# pcb_univ_3-8-0-x-rev2.net
KiCad netlist of a schematic drawn in EAGLE
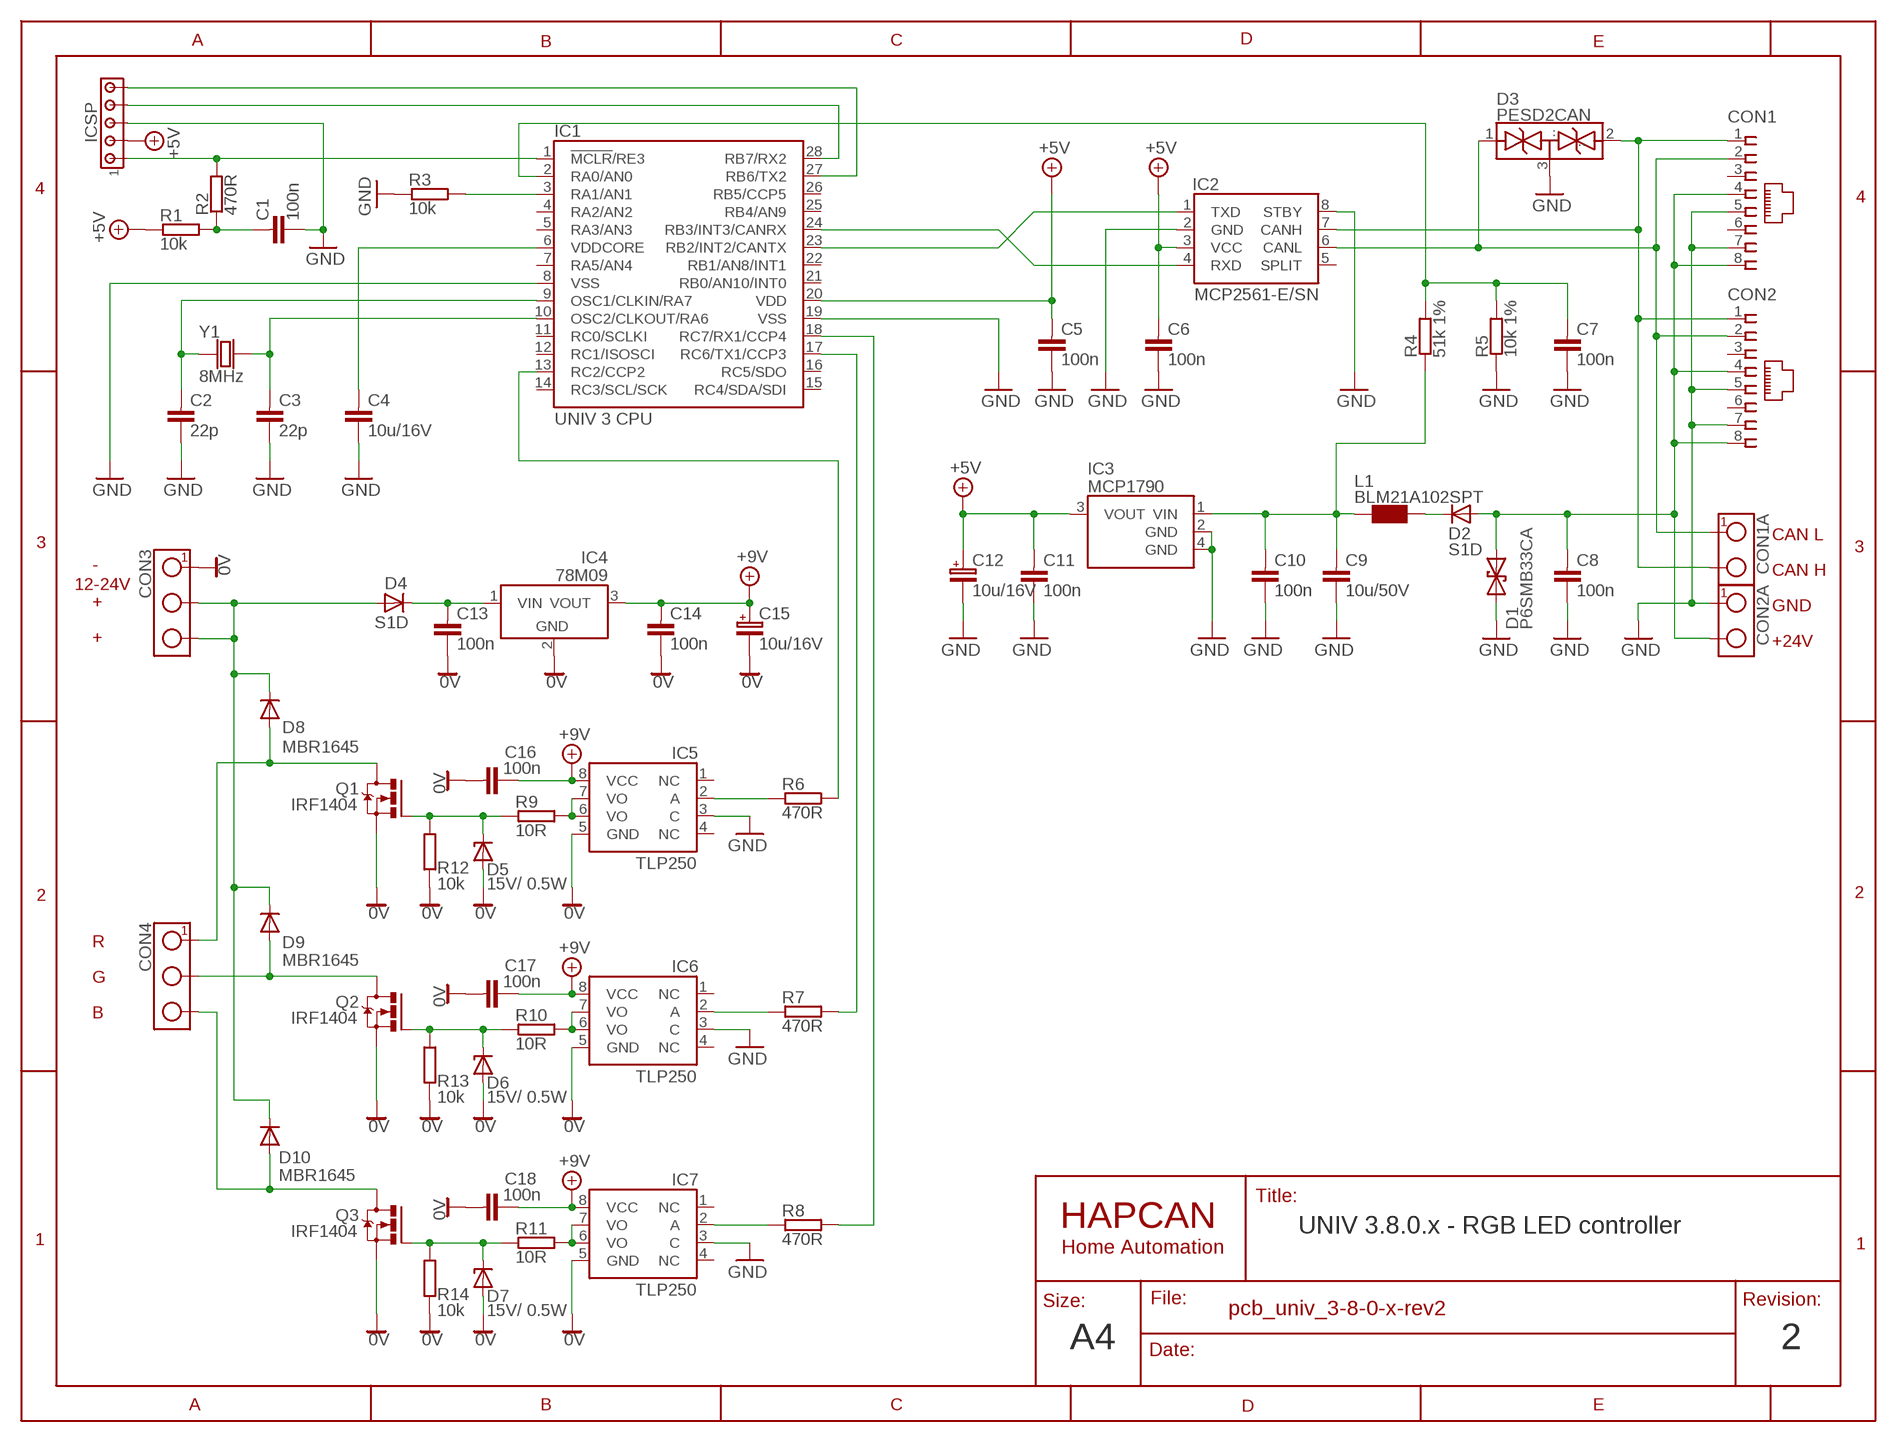
[diagram p0: schematic, sheet 1]

(export (version "E")
  (design (tool "Eeschema 10.0.6"))
  (components
    (comp (ref "C1")
      (value "100n")
      (footprint "eagle-import:0805")
      (libsource (lib "eagle-import") (part "CAPACITOR0805"))
    )
    (comp (ref "C2")
      (value "22p")
      (footprint "eagle-import:0805")
      (libsource (lib "eagle-import") (part "CAPACITOR0805"))
    )
    (comp (ref "C3")
      (value "22p")
      (footprint "eagle-import:0805")
      (libsource (lib "eagle-import") (part "CAPACITOR0805"))
    )
    (comp (ref "C4")
      (value "10u/16V")
      (footprint "eagle-import:0805")
      (libsource (lib "eagle-import") (part "CAPACITOR0805"))
    )
    (comp (ref "C5")
      (value "100n")
      (footprint "eagle-import:0805")
      (libsource (lib "eagle-import") (part "CAPACITOR0805"))
    )
    (comp (ref "C6")
      (value "100n")
      (footprint "eagle-import:0805")
      (libsource (lib "eagle-import") (part "CAPACITOR0805"))
    )
    (comp (ref "C7")
      (value "100n")
      (footprint "eagle-import:0805")
      (libsource (lib "eagle-import") (part "CAPACITOR0805"))
    )
    (comp (ref "C8")
      (value "100n")
      (footprint "eagle-import:0805")
      (libsource (lib "eagle-import") (part "CAPACITOR0805"))
    )
    (comp (ref "C9")
      (value "10u/50V")
      (footprint "eagle-import:1210")
      (libsource (lib "eagle-import") (part "CAPACITOR1210"))
    )
    (comp (ref "C10")
      (value "100n")
      (footprint "eagle-import:0805")
      (libsource (lib "eagle-import") (part "CAPACITOR0805"))
    )
    (comp (ref "C11")
      (value "100n")
      (footprint "eagle-import:0805")
      (libsource (lib "eagle-import") (part "CAPACITOR0805"))
    )
    (comp (ref "C12")
      (value "10u/16V")
      (footprint "eagle-import:SMC_B")
      (libsource (lib "eagle-import") (part "CAPACITOR-POLARIZED-SMC_B"))
    )
    (comp (ref "C13")
      (value "100n")
      (footprint "eagle-import:0805")
      (libsource (lib "eagle-import") (part "CAPACITOR0805"))
    )
    (comp (ref "C14")
      (value "100n")
      (footprint "eagle-import:0805")
      (libsource (lib "eagle-import") (part "CAPACITOR0805"))
    )
    (comp (ref "C15")
      (value "10u/16V")
      (footprint "eagle-import:SMC_B")
      (libsource (lib "eagle-import") (part "CAPACITOR-POLARIZED-SMC_B"))
    )
    (comp (ref "C16")
      (value "100n")
      (footprint "eagle-import:0805")
      (libsource (lib "eagle-import") (part "CAPACITOR0805"))
    )
    (comp (ref "C17")
      (value "100n")
      (footprint "eagle-import:0805")
      (libsource (lib "eagle-import") (part "CAPACITOR0805"))
    )
    (comp (ref "C18")
      (value "100n")
      (footprint "eagle-import:0805")
      (libsource (lib "eagle-import") (part "CAPACITOR0805"))
    )
    (comp (ref "CON1")
      (value "RJ45-SOCKET")
      (footprint "eagle-import:RJ45-PCB-SOCKET")
      (libsource (lib "eagle-import") (part "RJ45-SOCKET"))
    )
    (comp (ref "CON1A")
      (value "TERMINAL-2")
      (footprint "eagle-import:ARK2-5X10,5MM")
      (libsource (lib "eagle-import") (part "TERMINAL-2-5X10,5MM"))
    )
    (comp (ref "CON2")
      (value "RJ45-SOCKET")
      (footprint "eagle-import:RJ45-PCB-SOCKET")
      (libsource (lib "eagle-import") (part "RJ45-SOCKET"))
    )
    (comp (ref "CON2A")
      (value "TERMINAL-2")
      (footprint "eagle-import:ARK2-5X10,5MM")
      (libsource (lib "eagle-import") (part "TERMINAL-2-5X10,5MM"))
    )
    (comp (ref "CON3")
      (value "TERMINAL-3")
      (footprint "eagle-import:ARK3-5X10.5MM")
      (libsource (lib "eagle-import") (part "TERMINAL-3-5X10.5MM"))
    )
    (comp (ref "CON4")
      (value "TERMINAL-3")
      (footprint "eagle-import:ARK3-5X10.5MM")
      (libsource (lib "eagle-import") (part "TERMINAL-3-5X10.5MM"))
    )
    (comp (ref "D1")
      (value "P6SMB33CA")
      (footprint "eagle-import:DO-214_TRANSIL2")
      (libsource (lib "eagle-import") (part "DIODE_TRANSIL2"))
    )
    (comp (ref "D2")
      (value "S1D")
      (footprint "eagle-import:DO-214")
      (libsource (lib "eagle-import") (part "DIODE_DO-214"))
    )
    (comp (ref "D3")
      (value "PESD2CAN")
      (footprint "eagle-import:SOT-23")
      (libsource (lib "eagle-import") (part "PESD2CANSOT-23"))
    )
    (comp (ref "D4")
      (value "S1D")
      (footprint "eagle-import:DO-214")
      (libsource (lib "eagle-import") (part "DIODE_DO-214"))
    )
    (comp (ref "D5")
      (value "15V/ 0.5W")
      (footprint "eagle-import:SOD-80")
      (libsource (lib "eagle-import") (part "DIODE_ZENER_SOD-80"))
    )
    (comp (ref "D6")
      (value "15V/ 0.5W")
      (footprint "eagle-import:SOD-80")
      (libsource (lib "eagle-import") (part "DIODE_ZENER_SOD-80"))
    )
    (comp (ref "D7")
      (value "15V/ 0.5W")
      (footprint "eagle-import:SOD-80")
      (libsource (lib "eagle-import") (part "DIODE_ZENER_SOD-80"))
    )
    (comp (ref "D8")
      (value "MBR1645")
      (footprint "eagle-import:TO220V-2")
      (libsource (lib "eagle-import") (part "DIODE_TO220V"))
    )
    (comp (ref "D9")
      (value "MBR1645")
      (footprint "eagle-import:TO220V-2")
      (libsource (lib "eagle-import") (part "DIODE_TO220V"))
    )
    (comp (ref "D10")
      (value "MBR1645")
      (footprint "eagle-import:TO220V-2")
      (libsource (lib "eagle-import") (part "DIODE_TO220V"))
    )
    (comp (ref "IC1")
      (value "UNIV 3 CPU")
      (footprint "eagle-import:UNIV3CPU")
      (libsource (lib "eagle-import") (part "UNIV3CPU"))
    )
    (comp (ref "IC2")
      (value "MCP2561-E/SN")
      (footprint "eagle-import:SO-08")
      (libsource (lib "eagle-import") (part "MCP2561-E/SN"))
    )
    (comp (ref "IC3")
      (value "MCP1790")
      (footprint "eagle-import:SOT-223")
      (libsource (lib "eagle-import") (part "MCP1790"))
    )
    (comp (ref "IC4")
      (value "78M09")
      (footprint "eagle-import:TO-252")
      (libsource (lib "eagle-import") (part "78XX-TO-252"))
    )
    (comp (ref "IC5")
      (value "TLP250")
      (footprint "eagle-import:DIL-08W")
      (libsource (lib "eagle-import") (part "TLP250_WIDE"))
    )
    (comp (ref "IC6")
      (value "TLP250")
      (footprint "eagle-import:DIL-08W")
      (libsource (lib "eagle-import") (part "TLP250_WIDE"))
    )
    (comp (ref "IC7")
      (value "TLP250")
      (footprint "eagle-import:DIL-08W")
      (libsource (lib "eagle-import") (part "TLP250_WIDE"))
    )
    (comp (ref "ICSP")
      (value "HEADER5")
      (footprint "eagle-import:SIP-5")
      (libsource (lib "eagle-import") (part "HEADER5"))
    )
    (comp (ref "L1")
      (value "BLM21A102SPT")
      (footprint "eagle-import:0805@1")
      (libsource (lib "eagle-import") (part "BLMXXX"))
    )
    (comp (ref "Q1")
      (value "IRF1404")
      (footprint "eagle-import:TO220V")
      (libsource (lib "eagle-import") (part "MOSFET-N"))
    )
    (comp (ref "Q2")
      (value "IRF1404")
      (footprint "eagle-import:TO220V")
      (libsource (lib "eagle-import") (part "MOSFET-N"))
    )
    (comp (ref "Q3")
      (value "IRF1404")
      (footprint "eagle-import:TO220V")
      (libsource (lib "eagle-import") (part "MOSFET-N"))
    )
    (comp (ref "R1")
      (value "10k")
      (footprint "eagle-import:0805")
      (libsource (lib "eagle-import") (part "RESISTOR0805"))
    )
    (comp (ref "R2")
      (value "470R")
      (footprint "eagle-import:0805")
      (libsource (lib "eagle-import") (part "RESISTOR0805"))
    )
    (comp (ref "R3")
      (value "10k")
      (footprint "eagle-import:0805")
      (libsource (lib "eagle-import") (part "RESISTOR0805"))
    )
    (comp (ref "R4")
      (value "51k 1%")
      (footprint "eagle-import:0805")
      (libsource (lib "eagle-import") (part "RESISTOR0805"))
    )
    (comp (ref "R5")
      (value "10k 1%")
      (footprint "eagle-import:0805")
      (libsource (lib "eagle-import") (part "RESISTOR0805"))
    )
    (comp (ref "R6")
      (value "470R")
      (footprint "eagle-import:0805")
      (libsource (lib "eagle-import") (part "RESISTOR0805"))
    )
    (comp (ref "R7")
      (value "470R")
      (footprint "eagle-import:0805")
      (libsource (lib "eagle-import") (part "RESISTOR0805"))
    )
    (comp (ref "R8")
      (value "470R")
      (footprint "eagle-import:0805")
      (libsource (lib "eagle-import") (part "RESISTOR0805"))
    )
    (comp (ref "R9")
      (value "10R")
      (footprint "eagle-import:0805")
      (libsource (lib "eagle-import") (part "RESISTOR0805"))
    )
    (comp (ref "R10")
      (value "10R")
      (footprint "eagle-import:0805")
      (libsource (lib "eagle-import") (part "RESISTOR0805"))
    )
    (comp (ref "R11")
      (value "10R")
      (footprint "eagle-import:0805")
      (libsource (lib "eagle-import") (part "RESISTOR0805"))
    )
    (comp (ref "R12")
      (value "10k")
      (footprint "eagle-import:0805")
      (libsource (lib "eagle-import") (part "RESISTOR0805"))
    )
    (comp (ref "R13")
      (value "10k")
      (footprint "eagle-import:0805")
      (libsource (lib "eagle-import") (part "RESISTOR0805"))
    )
    (comp (ref "R14")
      (value "10k")
      (footprint "eagle-import:0805")
      (libsource (lib "eagle-import") (part "RESISTOR0805"))
    )
    (comp (ref "Y1")
      (value "8MHz")
      (footprint "eagle-import:CRYSTAL-HC49V")
      (libsource (lib "eagle-import") (part "CRYSTAL-HC49V"))
    )
  )
  (nets
    (net (code "1") (name "+5V") (class "Default")
      (node (ref "C11") (pin "1") (pinfunction "1_1") (pintype "passive"))
      (node (ref "C12") (pin "+") (pinfunction "1_+") (pintype "passive"))
      (node (ref "C5") (pin "1") (pinfunction "1_1") (pintype "passive"))
      (node (ref "C6") (pin "1") (pinfunction "1_1") (pintype "passive"))
      (node (ref "IC1") (pin "20") (pinfunction "VDD_20") (pintype "bidirectional"))
      (node (ref "IC2") (pin "3") (pinfunction "VCC_3") (pintype "bidirectional"))
      (node (ref "IC3") (pin "3") (pinfunction "VOUT_3") (pintype "bidirectional"))
      (node (ref "ICSP") (pin "2") (pinfunction "2_2") (pintype "passive"))
      (node (ref "R1") (pin "1") (pinfunction "1_1") (pintype "passive"))
    )
    (net (code "2") (name "+9V") (class "Default")
      (node (ref "C14") (pin "1") (pinfunction "1_1") (pintype "passive"))
      (node (ref "C15") (pin "+") (pinfunction "1_+") (pintype "passive"))
      (node (ref "C16") (pin "2") (pinfunction "2_2") (pintype "passive"))
      (node (ref "C17") (pin "2") (pinfunction "2_2") (pintype "passive"))
      (node (ref "C18") (pin "2") (pinfunction "2_2") (pintype "passive"))
      (node (ref "IC4") (pin "3") (pinfunction "VOUT_3") (pintype "bidirectional"))
      (node (ref "IC5") (pin "8") (pinfunction "VCC_8") (pintype "bidirectional"))
      (node (ref "IC6") (pin "8") (pinfunction "VCC_8") (pintype "bidirectional"))
      (node (ref "IC7") (pin "8") (pinfunction "VCC_8") (pintype "bidirectional"))
    )
    (net (code "3") (name "0V") (class "Default")
      (node (ref "C13") (pin "2") (pinfunction "2_2") (pintype "passive"))
      (node (ref "C14") (pin "2") (pinfunction "2_2") (pintype "passive"))
      (node (ref "C15") (pin "-") (pinfunction "2_-") (pintype "passive"))
      (node (ref "C16") (pin "1") (pinfunction "1_1") (pintype "passive"))
      (node (ref "C17") (pin "1") (pinfunction "1_1") (pintype "passive"))
      (node (ref "C18") (pin "1") (pinfunction "1_1") (pintype "passive"))
      (node (ref "CON3") (pin "1") (pinfunction "1_1") (pintype "passive"))
      (node (ref "D5") (pin "A") (pinfunction "A_A") (pintype "passive"))
      (node (ref "D6") (pin "A") (pinfunction "A_A") (pintype "passive"))
      (node (ref "D7") (pin "A") (pinfunction "A_A") (pintype "passive"))
      (node (ref "IC4") (pin "2") (pinfunction "GND_2") (pintype "bidirectional"))
      (node (ref "IC5") (pin "5") (pinfunction "GND_5") (pintype "bidirectional"))
      (node (ref "IC6") (pin "5") (pinfunction "GND_5") (pintype "bidirectional"))
      (node (ref "IC7") (pin "5") (pinfunction "GND_5") (pintype "bidirectional"))
      (node (ref "Q1") (pin "3") (pinfunction "S_3") (pintype "passive"))
      (node (ref "Q2") (pin "3") (pinfunction "S_3") (pintype "passive"))
      (node (ref "Q3") (pin "3") (pinfunction "S_3") (pintype "passive"))
      (node (ref "R12") (pin "1") (pinfunction "1_1") (pintype "passive"))
      (node (ref "R13") (pin "1") (pinfunction "1_1") (pintype "passive"))
      (node (ref "R14") (pin "1") (pinfunction "1_1") (pintype "passive"))
    )
    (net (code "4") (name "GND") (class "Default")
      (node (ref "C1") (pin "2") (pinfunction "2_2") (pintype "passive"))
      (node (ref "C10") (pin "2") (pinfunction "2_2") (pintype "passive"))
      (node (ref "C11") (pin "2") (pinfunction "2_2") (pintype "passive"))
      (node (ref "C12") (pin "-") (pinfunction "2_-") (pintype "passive"))
      (node (ref "C2") (pin "2") (pinfunction "2_2") (pintype "passive"))
      (node (ref "C3") (pin "2") (pinfunction "2_2") (pintype "passive"))
      (node (ref "C4") (pin "2") (pinfunction "2_2") (pintype "passive"))
      (node (ref "C5") (pin "2") (pinfunction "2_2") (pintype "passive"))
      (node (ref "C6") (pin "2") (pinfunction "2_2") (pintype "passive"))
      (node (ref "C7") (pin "2") (pinfunction "2_2") (pintype "passive"))
      (node (ref "C8") (pin "2") (pinfunction "2_2") (pintype "passive"))
      (node (ref "C9") (pin "2") (pinfunction "2_2") (pintype "passive"))
      (node (ref "CON1") (pin "5") (pinfunction "5_5") (pintype "passive"))
      (node (ref "CON1") (pin "7") (pinfunction "7_7") (pintype "passive"))
      (node (ref "CON2") (pin "5") (pinfunction "5_5") (pintype "passive"))
      (node (ref "CON2") (pin "7") (pinfunction "7_7") (pintype "passive"))
      (node (ref "CON2A") (pin "1") (pinfunction "1_1") (pintype "passive"))
      (node (ref "D1") (pin "A") (pinfunction "1_A") (pintype "passive"))
      (node (ref "D3") (pin "3") (pinfunction "..._3") (pintype "bidirectional"))
      (node (ref "IC1") (pin "19") (pinfunction "VSS_19") (pintype "bidirectional"))
      (node (ref "IC1") (pin "8") (pinfunction "VSS_8") (pintype "bidirectional"))
      (node (ref "IC2") (pin "2") (pinfunction "GND_2") (pintype "bidirectional"))
      (node (ref "IC2") (pin "8") (pinfunction "STBY_8") (pintype "bidirectional"))
      (node (ref "IC3") (pin "2") (pinfunction "GND_2") (pintype "bidirectional"))
      (node (ref "IC3") (pin "4") (pinfunction "GND_4") (pintype "bidirectional"))
      (node (ref "IC5") (pin "3") (pinfunction "C_3") (pintype "bidirectional"))
      (node (ref "IC6") (pin "3") (pinfunction "C_3") (pintype "bidirectional"))
      (node (ref "IC7") (pin "3") (pinfunction "C_3") (pintype "bidirectional"))
      (node (ref "ICSP") (pin "3") (pinfunction "3_3") (pintype "passive"))
      (node (ref "R3") (pin "1") (pinfunction "1_1") (pintype "passive"))
      (node (ref "R5") (pin "1") (pinfunction "1_1") (pintype "passive"))
    )
    (net (code "5") (name "Net-(C1-Pad1)") (class "Default")
      (node (ref "C1") (pin "1") (pinfunction "1_1") (pintype "passive"))
      (node (ref "R1") (pin "2") (pinfunction "2_2") (pintype "passive"))
      (node (ref "R2") (pin "1") (pinfunction "1_1") (pintype "passive"))
    )
    (net (code "6") (name "Net-(D1-2)") (class "Default")
      (node (ref "C8") (pin "1") (pinfunction "1_1") (pintype "passive"))
      (node (ref "CON1") (pin "4") (pinfunction "4_4") (pintype "passive"))
      (node (ref "CON1") (pin "8") (pinfunction "8_8") (pintype "passive"))
      (node (ref "CON2") (pin "4") (pinfunction "4_4") (pintype "passive"))
      (node (ref "CON2") (pin "8") (pinfunction "8_8") (pintype "passive"))
      (node (ref "CON2A") (pin "2") (pinfunction "2_2") (pintype "passive"))
      (node (ref "D1") (pin "C") (pinfunction "2_C") (pintype "passive"))
      (node (ref "D2") (pin "A") (pinfunction "A_A") (pintype "passive"))
    )
    (net (code "7") (name "Net-(D2-PadC)") (class "Default")
      (node (ref "D2") (pin "C") (pinfunction "C_C") (pintype "passive"))
      (node (ref "L1") (pin "2") (pinfunction "2_2") (pintype "passive"))
    )
    (net (code "8") (name "Net-(D3-.)") (class "Default")
      (node (ref "CON1") (pin "2") (pinfunction "2_2") (pintype "passive"))
      (node (ref "CON1A") (pin "1") (pinfunction "1_1") (pintype "passive"))
      (node (ref "CON2") (pin "2") (pinfunction "2_2") (pintype "passive"))
      (node (ref "D3") (pin "1") (pinfunction "._1") (pintype "bidirectional"))
      (node (ref "IC2") (pin "6") (pinfunction "CANL_6") (pintype "bidirectional"))
    )
    (net (code "9") (name "Net-(D3-..)") (class "Default")
      (node (ref "CON1") (pin "1") (pinfunction "1_1") (pintype "passive"))
      (node (ref "CON1A") (pin "2") (pinfunction "2_2") (pintype "passive"))
      (node (ref "CON2") (pin "1") (pinfunction "1_1") (pintype "passive"))
      (node (ref "D3") (pin "2") (pinfunction ".._2") (pintype "bidirectional"))
      (node (ref "IC2") (pin "7") (pinfunction "CANH_7") (pintype "bidirectional"))
    )
    (net (code "10") (name "Net-(D8-A)") (class "Default")
      (node (ref "CON4") (pin "1") (pinfunction "1_1") (pintype "passive"))
      (node (ref "D8") (pin "3") (pinfunction "A_3") (pintype "passive"))
      (node (ref "Q1") (pin "2") (pinfunction "D_2") (pintype "passive"))
    )
    (net (code "11") (name "Net-(D9-A)") (class "Default")
      (node (ref "CON4") (pin "2") (pinfunction "2_2") (pintype "passive"))
      (node (ref "D9") (pin "3") (pinfunction "A_3") (pintype "passive"))
      (node (ref "Q2") (pin "2") (pinfunction "D_2") (pintype "passive"))
    )
    (net (code "12") (name "Net-(D10-A)") (class "Default")
      (node (ref "CON4") (pin "3") (pinfunction "3_3") (pintype "passive"))
      (node (ref "D10") (pin "3") (pinfunction "A_3") (pintype "passive"))
      (node (ref "Q3") (pin "2") (pinfunction "D_2") (pintype "passive"))
    )
    (net (code "13") (name "Net-(D10-C)") (class "Default")
      (node (ref "CON3") (pin "2") (pinfunction "2_2") (pintype "passive"))
      (node (ref "CON3") (pin "3") (pinfunction "3_3") (pintype "passive"))
      (node (ref "D10") (pin "1") (pinfunction "C_1") (pintype "passive"))
      (node (ref "D4") (pin "A") (pinfunction "A_A") (pintype "passive"))
      (node (ref "D8") (pin "1") (pinfunction "C_1") (pintype "passive"))
      (node (ref "D9") (pin "1") (pinfunction "C_1") (pintype "passive"))
    )
    (net (code "14") (name "Net-(IC1-OSC1{slash}CLKIN{slash}RA7)") (class "Default")
      (node (ref "C2") (pin "1") (pinfunction "1_1") (pintype "passive"))
      (node (ref "IC1") (pin "9") (pinfunction "OSC1/CLKIN/RA7_9") (pintype "bidirectional"))
      (node (ref "Y1") (pin "1") (pinfunction "1_1") (pintype "passive"))
    )
    (net (code "15") (name "Net-(IC1-OSC2{slash}CLKOUT{slash}RA6)") (class "Default")
      (node (ref "C3") (pin "1") (pinfunction "1_1") (pintype "passive"))
      (node (ref "IC1") (pin "10") (pinfunction "OSC2/CLKOUT/RA6_10") (pintype "bidirectional"))
      (node (ref "Y1") (pin "2") (pinfunction "2_2") (pintype "passive"))
    )
    (net (code "16") (name "Net-(IC1-RA0{slash}AN0)") (class "Default")
      (node (ref "C7") (pin "1") (pinfunction "1_1") (pintype "passive"))
      (node (ref "IC1") (pin "2") (pinfunction "RA0/AN0_2") (pintype "bidirectional"))
      (node (ref "R4") (pin "2") (pinfunction "2_2") (pintype "passive"))
      (node (ref "R5") (pin "2") (pinfunction "2_2") (pintype "passive"))
    )
    (net (code "17") (name "Net-(IC1-RA1{slash}AN1)") (class "Default")
      (node (ref "IC1") (pin "3") (pinfunction "RA1/AN1_3") (pintype "bidirectional"))
      (node (ref "R3") (pin "2") (pinfunction "2_2") (pintype "passive"))
    )
    (net (code "18") (name "Net-(IC1-RB2{slash}INT2{slash}CANTX)") (class "Default")
      (node (ref "IC1") (pin "23") (pinfunction "RB2/INT2/CANTX_23") (pintype "bidirectional"))
      (node (ref "IC2") (pin "1") (pinfunction "TXD_1") (pintype "bidirectional"))
    )
    (net (code "19") (name "Net-(IC1-RB3{slash}INT3{slash}CANRX)") (class "Default")
      (node (ref "IC1") (pin "24") (pinfunction "RB3/INT3/CANRX_24") (pintype "bidirectional"))
      (node (ref "IC2") (pin "4") (pinfunction "RXD_4") (pintype "bidirectional"))
    )
    (net (code "20") (name "Net-(IC1-RB6{slash}TX2)") (class "Default")
      (node (ref "IC1") (pin "27") (pinfunction "RB6/TX2_27") (pintype "bidirectional"))
      (node (ref "ICSP") (pin "5") (pinfunction "5_5") (pintype "passive"))
    )
    (net (code "21") (name "Net-(IC1-RB7{slash}RX2)") (class "Default")
      (node (ref "IC1") (pin "28") (pinfunction "RB7/RX2_28") (pintype "bidirectional"))
      (node (ref "ICSP") (pin "4") (pinfunction "4_4") (pintype "passive"))
    )
    (net (code "22") (name "Net-(IC1-RC2{slash}CCP2)") (class "Default")
      (node (ref "IC1") (pin "13") (pinfunction "RC2/CCP2_13") (pintype "bidirectional"))
      (node (ref "R6") (pin "2") (pinfunction "2_2") (pintype "passive"))
    )
    (net (code "23") (name "Net-(IC1-RC6{slash}TX1{slash}CCP3)") (class "Default")
      (node (ref "IC1") (pin "17") (pinfunction "RC6/TX1/CCP3_17") (pintype "bidirectional"))
      (node (ref "R7") (pin "2") (pinfunction "2_2") (pintype "passive"))
    )
    (net (code "24") (name "Net-(IC1-RC7{slash}RX1{slash}CCP4)") (class "Default")
      (node (ref "IC1") (pin "18") (pinfunction "RC7/RX1/CCP4_18") (pintype "bidirectional"))
      (node (ref "R8") (pin "2") (pinfunction "2_2") (pintype "passive"))
    )
    (net (code "25") (name "Net-(IC1-VDDCORE)") (class "Default")
      (node (ref "C4") (pin "1") (pinfunction "1_1") (pintype "passive"))
      (node (ref "IC1") (pin "6") (pinfunction "VDDCORE_6") (pintype "bidirectional"))
    )
    (net (code "26") (name "Net-(IC1-~{MCLR}{slash}RE3)") (class "Default")
      (node (ref "IC1") (pin "1") (pinfunction "~{MCLR}/RE3_1") (pintype "bidirectional"))
      (node (ref "ICSP") (pin "1") (pinfunction "1_1") (pintype "passive"))
      (node (ref "R2") (pin "2") (pinfunction "2_2") (pintype "passive"))
    )
    (net (code "27") (name "Net-(IC3-VIN)") (class "Default")
      (node (ref "C10") (pin "1") (pinfunction "1_1") (pintype "passive"))
      (node (ref "C9") (pin "1") (pinfunction "1_1") (pintype "passive"))
      (node (ref "IC3") (pin "1") (pinfunction "VIN_1") (pintype "bidirectional"))
      (node (ref "L1") (pin "1") (pinfunction "1_1") (pintype "passive"))
      (node (ref "R4") (pin "1") (pinfunction "1_1") (pintype "passive"))
    )
    (net (code "28") (name "Net-(IC4-VIN)") (class "Default")
      (node (ref "C13") (pin "1") (pinfunction "1_1") (pintype "passive"))
      (node (ref "D4") (pin "C") (pinfunction "C_C") (pintype "passive"))
      (node (ref "IC4") (pin "1") (pinfunction "VIN_1") (pintype "bidirectional"))
    )
    (net (code "29") (name "Net-(IC5-A)") (class "Default")
      (node (ref "IC5") (pin "2") (pinfunction "A_2") (pintype "bidirectional"))
      (node (ref "R6") (pin "1") (pinfunction "1_1") (pintype "passive"))
    )
    (net (code "30") (name "Net-(IC5-VO-Pad6)") (class "Default")
      (node (ref "IC5") (pin "6") (pinfunction "VO_6") (pintype "bidirectional"))
      (node (ref "IC5") (pin "7") (pinfunction "VO_7") (pintype "bidirectional"))
      (node (ref "R9") (pin "2") (pinfunction "2_2") (pintype "passive"))
    )
    (net (code "31") (name "Net-(IC6-A)") (class "Default")
      (node (ref "IC6") (pin "2") (pinfunction "A_2") (pintype "bidirectional"))
      (node (ref "R7") (pin "1") (pinfunction "1_1") (pintype "passive"))
    )
    (net (code "32") (name "Net-(IC6-VO-Pad6)") (class "Default")
      (node (ref "IC6") (pin "6") (pinfunction "VO_6") (pintype "bidirectional"))
      (node (ref "IC6") (pin "7") (pinfunction "VO_7") (pintype "bidirectional"))
      (node (ref "R10") (pin "2") (pinfunction "2_2") (pintype "passive"))
    )
    (net (code "33") (name "Net-(IC7-A)") (class "Default")
      (node (ref "IC7") (pin "2") (pinfunction "A_2") (pintype "bidirectional"))
      (node (ref "R8") (pin "1") (pinfunction "1_1") (pintype "passive"))
    )
    (net (code "34") (name "Net-(IC7-VO-Pad6)") (class "Default")
      (node (ref "IC7") (pin "6") (pinfunction "VO_6") (pintype "bidirectional"))
      (node (ref "IC7") (pin "7") (pinfunction "VO_7") (pintype "bidirectional"))
      (node (ref "R11") (pin "2") (pinfunction "2_2") (pintype "passive"))
    )
    (net (code "35") (name "Net-(Q1-G)") (class "Default")
      (node (ref "D5") (pin "C") (pinfunction "C_C") (pintype "passive"))
      (node (ref "Q1") (pin "1") (pinfunction "G_1") (pintype "passive"))
      (node (ref "R12") (pin "2") (pinfunction "2_2") (pintype "passive"))
      (node (ref "R9") (pin "1") (pinfunction "1_1") (pintype "passive"))
    )
    (net (code "36") (name "Net-(Q2-G)") (class "Default")
      (node (ref "D6") (pin "C") (pinfunction "C_C") (pintype "passive"))
      (node (ref "Q2") (pin "1") (pinfunction "G_1") (pintype "passive"))
      (node (ref "R10") (pin "1") (pinfunction "1_1") (pintype "passive"))
      (node (ref "R13") (pin "2") (pinfunction "2_2") (pintype "passive"))
    )
    (net (code "37") (name "Net-(Q3-G)") (class "Default")
      (node (ref "D7") (pin "C") (pinfunction "C_C") (pintype "passive"))
      (node (ref "Q3") (pin "1") (pinfunction "G_1") (pintype "passive"))
      (node (ref "R11") (pin "1") (pinfunction "1_1") (pintype "passive"))
      (node (ref "R14") (pin "2") (pinfunction "2_2") (pintype "passive"))
    )
    (net (code "38") (name "unconnected-(CON1-Pad3)") (class "Default")
      (node (ref "CON1") (pin "3") (pinfunction "3_3") (pintype "passive"))
    )
    (net (code "39") (name "unconnected-(CON1-Pad6)") (class "Default")
      (node (ref "CON1") (pin "6") (pinfunction "6_6") (pintype "passive"))
    )
    (net (code "40") (name "unconnected-(CON2-Pad3)") (class "Default")
      (node (ref "CON2") (pin "3") (pinfunction "3_3") (pintype "passive"))
    )
    (net (code "41") (name "unconnected-(CON2-Pad6)") (class "Default")
      (node (ref "CON2") (pin "6") (pinfunction "6_6") (pintype "passive"))
    )
    (net (code "42") (name "unconnected-(IC1-RA2{slash}AN2-Pad4)") (class "Default")
      (node (ref "IC1") (pin "4") (pinfunction "RA2/AN2_4") (pintype "bidirectional"))
    )
    (net (code "43") (name "unconnected-(IC1-RA3{slash}AN3-Pad5)") (class "Default")
      (node (ref "IC1") (pin "5") (pinfunction "RA3/AN3_5") (pintype "bidirectional"))
    )
    (net (code "44") (name "unconnected-(IC1-RA5{slash}AN4-Pad7)") (class "Default")
      (node (ref "IC1") (pin "7") (pinfunction "RA5/AN4_7") (pintype "bidirectional"))
    )
    (net (code "45") (name "unconnected-(IC1-RB0{slash}AN10{slash}INT0-Pad21)") (class "Default")
      (node (ref "IC1") (pin "21") (pinfunction "RB0/AN10/INT0_21") (pintype "bidirectional"))
    )
    (net (code "46") (name "unconnected-(IC1-RB1{slash}AN8{slash}INT1-Pad22)") (class "Default")
      (node (ref "IC1") (pin "22") (pinfunction "RB1/AN8/INT1_22") (pintype "bidirectional"))
    )
    (net (code "47") (name "unconnected-(IC1-RB4{slash}AN9-Pad25)") (class "Default")
      (node (ref "IC1") (pin "25") (pinfunction "RB4/AN9_25") (pintype "bidirectional"))
    )
    (net (code "48") (name "unconnected-(IC1-RB5{slash}CCP5-Pad26)") (class "Default")
      (node (ref "IC1") (pin "26") (pinfunction "RB5/CCP5_26") (pintype "bidirectional"))
    )
    (net (code "49") (name "unconnected-(IC1-RC0{slash}SCLKI-Pad11)") (class "Default")
      (node (ref "IC1") (pin "11") (pinfunction "RC0/SCLKI_11") (pintype "bidirectional"))
    )
    (net (code "50") (name "unconnected-(IC1-RC1{slash}ISOSCI-Pad12)") (class "Default")
      (node (ref "IC1") (pin "12") (pinfunction "RC1/ISOSCI_12") (pintype "bidirectional"))
    )
    (net (code "51") (name "unconnected-(IC1-RC3{slash}SCL{slash}SCK-Pad14)") (class "Default")
      (node (ref "IC1") (pin "14") (pinfunction "RC3/SCL/SCK_14") (pintype "bidirectional"))
    )
    (net (code "52") (name "unconnected-(IC1-RC4{slash}SDA{slash}SDI-Pad15)") (class "Default")
      (node (ref "IC1") (pin "15") (pinfunction "RC4/SDA/SDI_15") (pintype "bidirectional"))
    )
    (net (code "53") (name "unconnected-(IC1-RC5{slash}SDO-Pad16)") (class "Default")
      (node (ref "IC1") (pin "16") (pinfunction "RC5/SDO_16") (pintype "bidirectional"))
    )
    (net (code "54") (name "unconnected-(IC2-SPLIT-Pad5)") (class "Default")
      (node (ref "IC2") (pin "5") (pinfunction "SPLIT_5") (pintype "bidirectional"))
    )
    (net (code "55") (name "unconnected-(IC5-NC-Pad1)") (class "Default")
      (node (ref "IC5") (pin "1") (pinfunction "NC_1") (pintype "bidirectional"))
    )
    (net (code "56") (name "unconnected-(IC5-NC-Pad4)") (class "Default")
      (node (ref "IC5") (pin "4") (pinfunction "NC_4") (pintype "bidirectional"))
    )
    (net (code "57") (name "unconnected-(IC6-NC-Pad1)") (class "Default")
      (node (ref "IC6") (pin "1") (pinfunction "NC_1") (pintype "bidirectional"))
    )
    (net (code "58") (name "unconnected-(IC6-NC-Pad4)") (class "Default")
      (node (ref "IC6") (pin "4") (pinfunction "NC_4") (pintype "bidirectional"))
    )
    (net (code "59") (name "unconnected-(IC7-NC-Pad1)") (class "Default")
      (node (ref "IC7") (pin "1") (pinfunction "NC_1") (pintype "bidirectional"))
    )
    (net (code "60") (name "unconnected-(IC7-NC-Pad4)") (class "Default")
      (node (ref "IC7") (pin "4") (pinfunction "NC_4") (pintype "bidirectional"))
    )
  )
)
